# mcp73123-breakout01.net
KiCad netlist of a schematic drawn in EAGLE
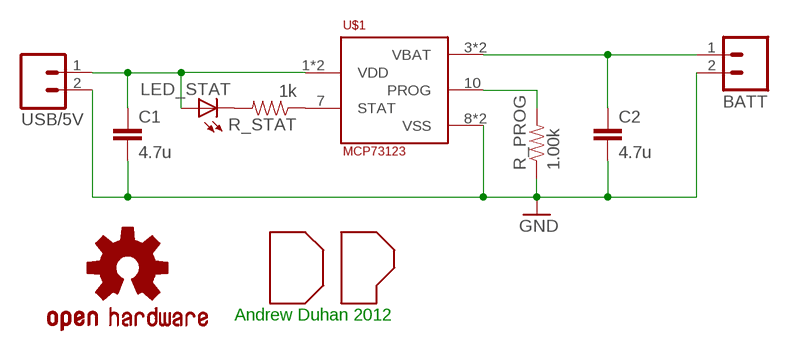
[diagram p0: schematic, sheet 1]

(export (version "E")
  (design (tool "Eeschema 10.0.6"))
  (components
    (comp (ref "BATT")
      (value "M02PTH")
      (footprint "eagle-import:1X02")
      (libsource (lib "eagle-import") (part "M02PTH"))
    )
    (comp (ref "C1")
      (value "4.7u")
      (footprint "eagle-import:0603-CAP")
      (libsource (lib "eagle-import") (part "CAP0603-CAP"))
    )
    (comp (ref "C2")
      (value "4.7u")
      (footprint "eagle-import:0603-CAP")
      (libsource (lib "eagle-import") (part "CAP0603-CAP"))
    )
    (comp (ref "LED_STAT")
      (value "LED1206")
      (footprint "eagle-import:LED-1206")
      (libsource (lib "eagle-import") (part "LED1206"))
    )
    (comp (ref "R_PROG")
      (value "1.00k")
      (footprint "eagle-import:0603-RES")
      (libsource (lib "eagle-import") (part "RESISTOR0603-RES"))
    )
    (comp (ref "R_STAT")
      (value "1k")
      (footprint "eagle-import:0603-RES")
      (libsource (lib "eagle-import") (part "RESISTOR0603-RES"))
    )
    (comp (ref "U$1")
      (value "MCP73123")
      (footprint "eagle-import:VDFN10")
      (libsource (lib "eagle-import") (part "MCP73123"))
    )
    (comp (ref "U$2")
      (value "DP_LOGO")
      (footprint "eagle-import:DP_LOGO")
      (libsource (lib "eagle-import") (part "DP_LOGO"))
    )
    (comp (ref "U$3")
      (value "OSHW-LOGOS")
      (footprint "eagle-import:OSHW-LOGO-S")
      (libsource (lib "eagle-import") (part "OSHW-LOGOS"))
    )
    (comp (ref "USB/5V")
      (value "M02PTH")
      (footprint "eagle-import:1X02")
      (libsource (lib "eagle-import") (part "M02PTH"))
    )
  )
  (nets
    (net (code "1") (name "GND") (class "Default")
      (node (ref "BATT") (pin "2") (pinfunction "2_2") (pintype "passive"))
      (node (ref "C1") (pin "2") (pinfunction "2_2") (pintype "passive"))
      (node (ref "C2") (pin "2") (pinfunction "2_2") (pintype "passive"))
      (node (ref "R_PROG") (pin "1") (pinfunction "1_1") (pintype "passive"))
      (node (ref "U$1") (pin "8") (pinfunction "VSS_8") (pintype "bidirectional"))
      (node (ref "U$1") (pin "9") (pinfunction "VSS_9") (pintype "bidirectional"))
      (node (ref "USB/5V") (pin "2") (pinfunction "2_2") (pintype "passive"))
    )
    (net (code "2") (name "Net-(BATT-Pad1)") (class "Default")
      (node (ref "BATT") (pin "1") (pinfunction "1_1") (pintype "passive"))
      (node (ref "C2") (pin "1") (pinfunction "1_1") (pintype "passive"))
      (node (ref "U$1") (pin "3") (pinfunction "VBAT_3") (pintype "bidirectional"))
      (node (ref "U$1") (pin "4") (pinfunction "VBAT_4") (pintype "bidirectional"))
    )
    (net (code "3") (name "Net-(C1-Pad1)") (class "Default")
      (node (ref "C1") (pin "1") (pinfunction "1_1") (pintype "passive"))
      (node (ref "LED_STAT") (pin "A") (pinfunction "A_A") (pintype "passive"))
      (node (ref "U$1") (pin "1") (pinfunction "VDD_1") (pintype "bidirectional"))
      (node (ref "U$1") (pin "2") (pinfunction "VDD_2") (pintype "bidirectional"))
      (node (ref "USB/5V") (pin "1") (pinfunction "1_1") (pintype "passive"))
    )
    (net (code "4") (name "Net-(LED_STAT-PadC)") (class "Default")
      (node (ref "LED_STAT") (pin "C") (pinfunction "C_C") (pintype "passive"))
      (node (ref "R_STAT") (pin "2") (pinfunction "2_2") (pintype "passive"))
    )
    (net (code "5") (name "Net-(U$1-PROG)") (class "Default")
      (node (ref "R_PROG") (pin "2") (pinfunction "2_2") (pintype "passive"))
      (node (ref "U$1") (pin "10") (pinfunction "PROG_10") (pintype "bidirectional"))
    )
    (net (code "6") (name "Net-(U$1-STAT)") (class "Default")
      (node (ref "R_STAT") (pin "1") (pinfunction "1_1") (pintype "passive"))
      (node (ref "U$1") (pin "7") (pinfunction "STAT_7") (pintype "bidirectional"))
    )
  )
)
